# untitled.net
KiCad netlist of a schematic drawn in EAGLE
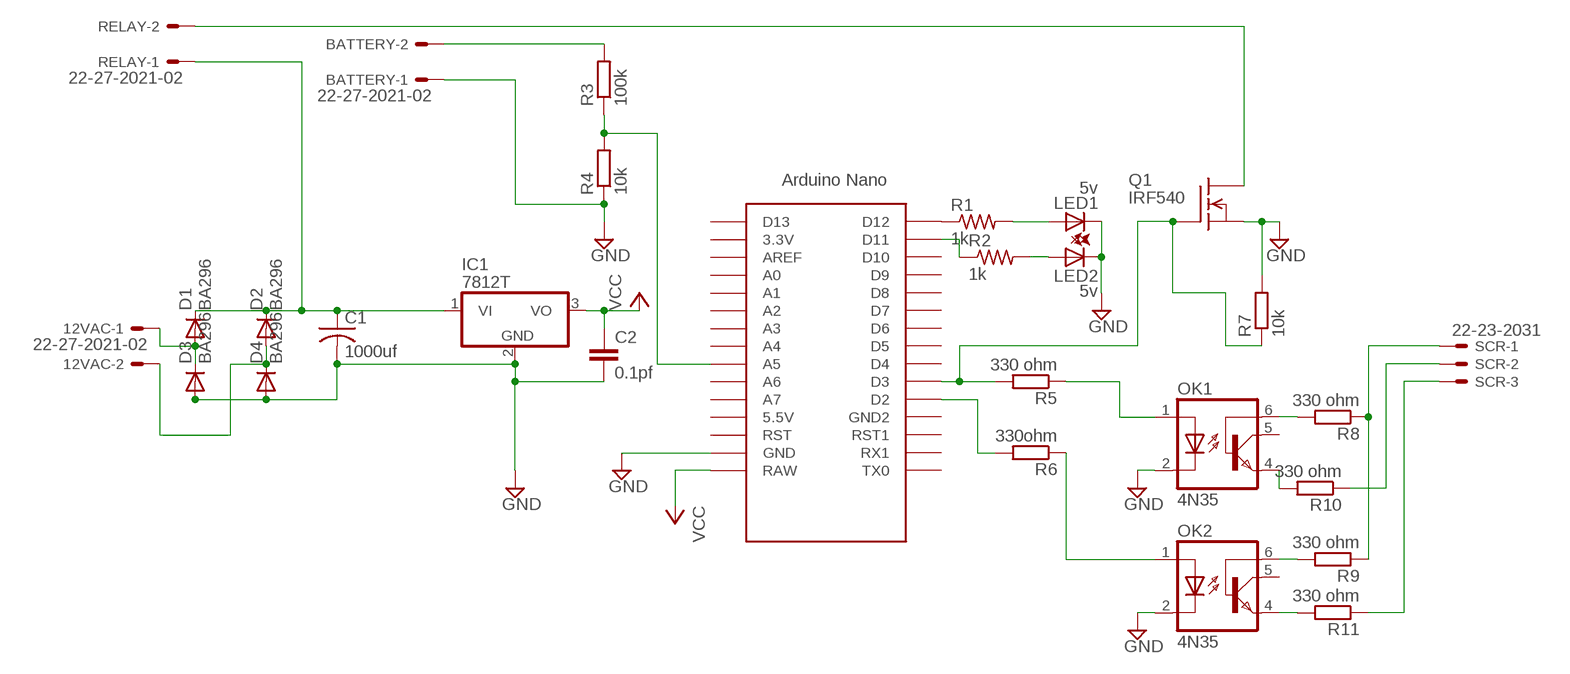
[diagram p0: schematic, sheet 1]

(export (version "E")
  (design (tool "Eeschema 10.0.6"))
  (components
    (comp (ref "12VAC")
      (value "22-27-2021-02")
      (footprint "eagle-import:6410-02")
      (libsource (lib "eagle-import") (part "22-?-0227-2021"))
    )
    (comp (ref "BATTERY")
      (value "22-27-2021-02")
      (footprint "eagle-import:6410-02")
      (libsource (lib "eagle-import") (part "22-?-0227-2021"))
    )
    (comp (ref "C1")
      (value "1000uf")
      (footprint "eagle-import:C050-025X075")
      (libsource (lib "eagle-import") (part "C-US050-025X075"))
    )
    (comp (ref "C2")
      (value "0.1pf")
      (footprint "eagle-import:C7.5B4")
      (libsource (lib "eagle-import") (part "C7.5/4"))
    )
    (comp (ref "D1")
      (value "BA296")
      (footprint "eagle-import:P2-15")
      (libsource (lib "eagle-import") (part "BA296"))
    )
    (comp (ref "D2")
      (value "BA296")
      (footprint "eagle-import:P2-15")
      (libsource (lib "eagle-import") (part "BA296"))
    )
    (comp (ref "D3")
      (value "BA296")
      (footprint "eagle-import:P2-15")
      (libsource (lib "eagle-import") (part "BA296"))
    )
    (comp (ref "D4")
      (value "BA296")
      (footprint "eagle-import:P2-15")
      (libsource (lib "eagle-import") (part "BA296"))
    )
    (comp (ref "IC1")
      (value "7812T")
      (footprint "eagle-import:TO220H")
      (libsource (lib "eagle-import") (part "78T12"))
    )
    (comp (ref "LED1")
      (value "5v")
      (footprint "eagle-import:LED_1206")
      (libsource (lib "eagle-import") (part "LED_E"))
    )
    (comp (ref "LED2")
      (value "5v")
      (footprint "eagle-import:LED_1206")
      (libsource (lib "eagle-import") (part "LED_E"))
    )
    (comp (ref "OK1")
      (value "4N35")
      (footprint "eagle-import:DIL06")
      (fields (field (name "MF") "FAIRCHILD SEMICONDUCTOR"))
      (libsource (lib "eagle-import") (part "4N35"))
    )
    (comp (ref "OK2")
      (value "4N35")
      (footprint "eagle-import:DIL06")
      (fields (field (name "MF") "FAIRCHILD SEMICONDUCTOR"))
      (libsource (lib "eagle-import") (part "4N35"))
    )
    (comp (ref "Q1")
      (value "IRF540")
      (footprint "eagle-import:TO220")
      (libsource (lib "eagle-import") (part "IRF540"))
    )
    (comp (ref "R1")
      (value "1k")
      (footprint "eagle-import:0207_2V")
      (libsource (lib "eagle-import") (part "R-US_0207/2V"))
    )
    (comp (ref "R2")
      (value "1k")
      (footprint "eagle-import:0207_2V")
      (libsource (lib "eagle-import") (part "R-US_0207/2V"))
    )
    (comp (ref "R3")
      (value "100k")
      (footprint "eagle-import:0207_10")
      (libsource (lib "eagle-import") (part "R0207/10"))
    )
    (comp (ref "R4")
      (value "10k")
      (footprint "eagle-import:0207_10")
      (libsource (lib "eagle-import") (part "R0207/10"))
    )
    (comp (ref "R5")
      (value "330 ohm")
      (footprint "eagle-import:0207_10")
      (libsource (lib "eagle-import") (part "R0207/10"))
    )
    (comp (ref "R6")
      (value "330ohm")
      (footprint "eagle-import:0207_10")
      (libsource (lib "eagle-import") (part "R0207/10"))
    )
    (comp (ref "R7")
      (value "10k")
      (footprint "eagle-import:0207_10")
      (libsource (lib "eagle-import") (part "R0207/10"))
    )
    (comp (ref "R8")
      (value "330 ohm")
      (footprint "eagle-import:0207_10")
      (libsource (lib "eagle-import") (part "R0207/10"))
    )
    (comp (ref "R9")
      (value "330 ohm")
      (footprint "eagle-import:0207_10")
      (libsource (lib "eagle-import") (part "R0207/10"))
    )
    (comp (ref "R10")
      (value "330 ohm")
      (footprint "eagle-import:0207_10")
      (libsource (lib "eagle-import") (part "R0207/10"))
    )
    (comp (ref "R11")
      (value "330 ohm")
      (footprint "eagle-import:0207_10")
      (libsource (lib "eagle-import") (part "R0207/10"))
    )
    (comp (ref "RELAY")
      (value "22-27-2021-02")
      (footprint "eagle-import:6410-02")
      (libsource (lib "eagle-import") (part "22-?-0227-2021"))
    )
    (comp (ref "SCR")
      (value "22-23-2031")
      (footprint "eagle-import:22-23-2031")
      (fields (field (name "MF") "MOLEX"))
      (libsource (lib "eagle-import") (part "22-23-2031"))
    )
    (comp (ref "U$1")
      (value "NANO")
      (footprint "eagle-import:NANO")
      (libsource (lib "eagle-import") (part "NANO"))
    )
  )
  (nets
    (net (code "1") (name "GND") (class "Default")
      (node (ref "BATTERY") (pin "1") (pinfunction "S_1") (pintype "passive"))
      (node (ref "C1") (pin "2") (pinfunction "2_2") (pintype "passive"))
      (node (ref "C2") (pin "2") (pinfunction "2_2") (pintype "passive"))
      (node (ref "D3") (pin "A") (pinfunction "A_A") (pintype "passive"))
      (node (ref "D4") (pin "A") (pinfunction "A_A") (pintype "passive"))
      (node (ref "IC1") (pin "2") (pinfunction "GND_2") (pintype "passive"))
      (node (ref "LED1") (pin "C") (pinfunction "C_C") (pintype "passive"))
      (node (ref "LED2") (pin "C") (pinfunction "C_C") (pintype "passive"))
      (node (ref "OK1") (pin "2") (pinfunction "C_2") (pintype "passive"))
      (node (ref "OK2") (pin "2") (pinfunction "C_2") (pintype "passive"))
      (node (ref "Q1") (pin "3") (pinfunction "S_3") (pintype "passive"))
      (node (ref "R4") (pin "1") (pinfunction "1_1") (pintype "passive"))
      (node (ref "R7") (pin "2") (pinfunction "2_2") (pintype "passive"))
      (node (ref "U$1") (pin "GND") (pinfunction "GND_GND") (pintype "bidirectional"))
    )
    (net (code "2") (name "Net-(12VACA-S)") (class "Default")
      (node (ref "12VAC") (pin "1") (pinfunction "S_1") (pintype "passive"))
      (node (ref "D1") (pin "A") (pinfunction "A_A") (pintype "passive"))
      (node (ref "D3") (pin "C") (pinfunction "C_C") (pintype "passive"))
    )
    (net (code "3") (name "Net-(12VACB-S)") (class "Default")
      (node (ref "12VAC") (pin "2") (pinfunction "S_2") (pintype "passive"))
      (node (ref "D2") (pin "A") (pinfunction "A_A") (pintype "passive"))
      (node (ref "D4") (pin "C") (pinfunction "C_C") (pintype "passive"))
    )
    (net (code "4") (name "Net-(BATTERYB-S)") (class "Default")
      (node (ref "BATTERY") (pin "2") (pinfunction "S_2") (pintype "passive"))
      (node (ref "R3") (pin "2") (pinfunction "2_2") (pintype "passive"))
    )
    (net (code "5") (name "Net-(IC1-VI)") (class "Default")
      (node (ref "C1") (pin "1") (pinfunction "1_1") (pintype "passive"))
      (node (ref "D1") (pin "C") (pinfunction "C_C") (pintype "passive"))
      (node (ref "D2") (pin "C") (pinfunction "C_C") (pintype "passive"))
      (node (ref "IC1") (pin "1") (pinfunction "VI_1") (pintype "input"))
      (node (ref "RELAY") (pin "1") (pinfunction "S_1") (pintype "passive"))
    )
    (net (code "6") (name "Net-(LED1-PadA)") (class "Default")
      (node (ref "LED1") (pin "A") (pinfunction "A_A") (pintype "passive"))
      (node (ref "R1") (pin "2") (pinfunction "2_2") (pintype "passive"))
    )
    (net (code "7") (name "Net-(LED2-PadA)") (class "Default")
      (node (ref "LED2") (pin "A") (pinfunction "A_A") (pintype "passive"))
      (node (ref "R2") (pin "2") (pinfunction "2_2") (pintype "passive"))
    )
    (net (code "8") (name "Net-(OK1-A)") (class "Default")
      (node (ref "OK1") (pin "1") (pinfunction "A_1") (pintype "passive"))
      (node (ref "R5") (pin "1") (pinfunction "1_1") (pintype "passive"))
    )
    (net (code "9") (name "Net-(OK1-BAS)") (class "Default")
      (node (ref "OK1") (pin "6") (pinfunction "BAS_6") (pintype "passive"))
      (node (ref "R8") (pin "2") (pinfunction "2_2") (pintype "passive"))
    )
    (net (code "10") (name "Net-(OK1-EMI)") (class "Default")
      (node (ref "OK1") (pin "4") (pinfunction "EMI_4") (pintype "passive"))
      (node (ref "R10") (pin "2") (pinfunction "2_2") (pintype "passive"))
    )
    (net (code "11") (name "Net-(OK2-A)") (class "Default")
      (node (ref "OK2") (pin "1") (pinfunction "A_1") (pintype "passive"))
      (node (ref "R6") (pin "1") (pinfunction "1_1") (pintype "passive"))
    )
    (net (code "12") (name "Net-(OK2-BAS)") (class "Default")
      (node (ref "OK2") (pin "6") (pinfunction "BAS_6") (pintype "passive"))
      (node (ref "R9") (pin "2") (pinfunction "2_2") (pintype "passive"))
    )
    (net (code "13") (name "Net-(OK2-EMI)") (class "Default")
      (node (ref "OK2") (pin "4") (pinfunction "EMI_4") (pintype "passive"))
      (node (ref "R11") (pin "2") (pinfunction "2_2") (pintype "passive"))
    )
    (net (code "14") (name "Net-(Q1-D)") (class "Default")
      (node (ref "Q1") (pin "2") (pinfunction "D_2") (pintype "passive"))
      (node (ref "RELAY") (pin "2") (pinfunction "S_2") (pintype "passive"))
    )
    (net (code "15") (name "Net-(Q1-G)") (class "Default")
      (node (ref "Q1") (pin "1") (pinfunction "G_1") (pintype "passive"))
      (node (ref "R5") (pin "2") (pinfunction "2_2") (pintype "passive"))
      (node (ref "R7") (pin "1") (pinfunction "1_1") (pintype "passive"))
      (node (ref "U$1") (pin "D3") (pinfunction "D3_D3") (pintype "bidirectional"))
    )
    (net (code "16") (name "Net-(R1-Pad1)") (class "Default")
      (node (ref "R1") (pin "1") (pinfunction "1_1") (pintype "passive"))
      (node (ref "U$1") (pin "D12") (pinfunction "D12_D12") (pintype "bidirectional"))
    )
    (net (code "17") (name "Net-(R2-Pad1)") (class "Default")
      (node (ref "R2") (pin "1") (pinfunction "1_1") (pintype "passive"))
      (node (ref "U$1") (pin "D11") (pinfunction "D11_D11") (pintype "bidirectional"))
    )
    (net (code "18") (name "Net-(R3-Pad1)") (class "Default")
      (node (ref "R3") (pin "1") (pinfunction "1_1") (pintype "passive"))
      (node (ref "R4") (pin "2") (pinfunction "2_2") (pintype "passive"))
      (node (ref "U$1") (pin "A5") (pinfunction "A5_A5") (pintype "bidirectional"))
    )
    (net (code "19") (name "Net-(R6-Pad2)") (class "Default")
      (node (ref "R6") (pin "2") (pinfunction "2_2") (pintype "passive"))
      (node (ref "U$1") (pin "D2") (pinfunction "D2_D2") (pintype "bidirectional"))
    )
    (net (code "20") (name "Net-(SCRA-S)") (class "Default")
      (node (ref "R8") (pin "1") (pinfunction "1_1") (pintype "passive"))
      (node (ref "R9") (pin "1") (pinfunction "1_1") (pintype "passive"))
      (node (ref "SCR") (pin "1") (pinfunction "S_1") (pintype "passive"))
    )
    (net (code "21") (name "Net-(SCRB-S)") (class "Default")
      (node (ref "R10") (pin "1") (pinfunction "1_1") (pintype "passive"))
      (node (ref "SCR") (pin "2") (pinfunction "S_2") (pintype "passive"))
    )
    (net (code "22") (name "Net-(SCRC-S)") (class "Default")
      (node (ref "R11") (pin "1") (pinfunction "1_1") (pintype "passive"))
      (node (ref "SCR") (pin "3") (pinfunction "S_3") (pintype "passive"))
    )
    (net (code "23") (name "VCC") (class "Default")
      (node (ref "C2") (pin "1") (pinfunction "1_1") (pintype "passive"))
      (node (ref "IC1") (pin "3") (pinfunction "VO_3") (pintype "passive"))
      (node (ref "U$1") (pin "RAW") (pinfunction "RAW_RAW") (pintype "bidirectional"))
    )
    (net (code "24") (name "unconnected-(OK1-COL-Pad5)") (class "Default")
      (node (ref "OK1") (pin "5") (pinfunction "COL_5") (pintype "passive"))
    )
    (net (code "25") (name "unconnected-(OK2-COL-Pad5)") (class "Default")
      (node (ref "OK2") (pin "5") (pinfunction "COL_5") (pintype "passive"))
    )
    (net (code "26") (name "unconnected-(U$1-5.5V-Pad5V)") (class "Default")
      (node (ref "U$1") (pin "5V") (pinfunction "5.5V_5V") (pintype "bidirectional"))
    )
    (net (code "27") (name "unconnected-(U$1-GND2-PadGND1)") (class "Default")
      (node (ref "U$1") (pin "GND1") (pinfunction "GND2_GND1") (pintype "bidirectional"))
    )
    (net (code "28") (name "unconnected-(U$1-Pad3.3V)") (class "Default")
      (node (ref "U$1") (pin "3.3V") (pinfunction "3.3V_3.3V") (pintype "bidirectional"))
    )
    (net (code "29") (name "unconnected-(U$1-PadA0)") (class "Default")
      (node (ref "U$1") (pin "A0") (pinfunction "A0_A0") (pintype "bidirectional"))
    )
    (net (code "30") (name "unconnected-(U$1-PadA1)") (class "Default")
      (node (ref "U$1") (pin "A1") (pinfunction "A1_A1") (pintype "bidirectional"))
    )
    (net (code "31") (name "unconnected-(U$1-PadA2)") (class "Default")
      (node (ref "U$1") (pin "A2") (pinfunction "A2_A2") (pintype "bidirectional"))
    )
    (net (code "32") (name "unconnected-(U$1-PadA3)") (class "Default")
      (node (ref "U$1") (pin "A3") (pinfunction "A3_A3") (pintype "bidirectional"))
    )
    (net (code "33") (name "unconnected-(U$1-PadA4)") (class "Default")
      (node (ref "U$1") (pin "A4") (pinfunction "A4_A4") (pintype "bidirectional"))
    )
    (net (code "34") (name "unconnected-(U$1-PadA6)") (class "Default")
      (node (ref "U$1") (pin "A6") (pinfunction "A6_A6") (pintype "bidirectional"))
    )
    (net (code "35") (name "unconnected-(U$1-PadA7)") (class "Default")
      (node (ref "U$1") (pin "A7") (pinfunction "A7_A7") (pintype "bidirectional"))
    )
    (net (code "36") (name "unconnected-(U$1-PadAREF)") (class "Default")
      (node (ref "U$1") (pin "AREF") (pinfunction "AREF_AREF") (pintype "bidirectional"))
    )
    (net (code "37") (name "unconnected-(U$1-PadD4)") (class "Default")
      (node (ref "U$1") (pin "D4") (pinfunction "D4_D4") (pintype "bidirectional"))
    )
    (net (code "38") (name "unconnected-(U$1-PadD5)") (class "Default")
      (node (ref "U$1") (pin "D5") (pinfunction "D5_D5") (pintype "bidirectional"))
    )
    (net (code "39") (name "unconnected-(U$1-PadD6)") (class "Default")
      (node (ref "U$1") (pin "D6") (pinfunction "D6_D6") (pintype "bidirectional"))
    )
    (net (code "40") (name "unconnected-(U$1-PadD7)") (class "Default")
      (node (ref "U$1") (pin "D7") (pinfunction "D7_D7") (pintype "bidirectional"))
    )
    (net (code "41") (name "unconnected-(U$1-PadD8)") (class "Default")
      (node (ref "U$1") (pin "D8") (pinfunction "D8_D8") (pintype "bidirectional"))
    )
    (net (code "42") (name "unconnected-(U$1-PadD9)") (class "Default")
      (node (ref "U$1") (pin "D9") (pinfunction "D9_D9") (pintype "bidirectional"))
    )
    (net (code "43") (name "unconnected-(U$1-PadD10)") (class "Default")
      (node (ref "U$1") (pin "D10") (pinfunction "D10_D10") (pintype "bidirectional"))
    )
    (net (code "44") (name "unconnected-(U$1-PadD13)") (class "Default")
      (node (ref "U$1") (pin "D13") (pinfunction "D13_D13") (pintype "bidirectional"))
    )
    (net (code "45") (name "unconnected-(U$1-PadICSP1)") (class "Default")
      (node (ref "U$1") (pin "ICSP1") (pinfunction "ICSP1_ICSP1") (pintype "bidirectional"))
    )
    (net (code "46") (name "unconnected-(U$1-PadICSP2)") (class "Default")
      (node (ref "U$1") (pin "ICSP2") (pinfunction "ICSP2_ICSP2") (pintype "bidirectional"))
    )
    (net (code "47") (name "unconnected-(U$1-PadICSP3)") (class "Default")
      (node (ref "U$1") (pin "ICSP3") (pinfunction "ICSP3_ICSP3") (pintype "bidirectional"))
    )
    (net (code "48") (name "unconnected-(U$1-PadICSP4)") (class "Default")
      (node (ref "U$1") (pin "ICSP4") (pinfunction "ICSP4_ICSP4") (pintype "bidirectional"))
    )
    (net (code "49") (name "unconnected-(U$1-PadICSP5)") (class "Default")
      (node (ref "U$1") (pin "ICSP5") (pinfunction "ICSP5_ICSP5") (pintype "bidirectional"))
    )
    (net (code "50") (name "unconnected-(U$1-PadICSP6)") (class "Default")
      (node (ref "U$1") (pin "ICSP6") (pinfunction "ICSP6_ICSP6") (pintype "bidirectional"))
    )
    (net (code "51") (name "unconnected-(U$1-PadRST)") (class "Default")
      (node (ref "U$1") (pin "RST") (pinfunction "RST_RST") (pintype "bidirectional"))
    )
    (net (code "52") (name "unconnected-(U$1-PadRST1)") (class "Default")
      (node (ref "U$1") (pin "RST1") (pinfunction "RST1_RST1") (pintype "bidirectional"))
    )
    (net (code "53") (name "unconnected-(U$1-PadRX1)") (class "Default")
      (node (ref "U$1") (pin "RX1") (pinfunction "RX1_RX1") (pintype "bidirectional"))
    )
    (net (code "54") (name "unconnected-(U$1-PadTX0)") (class "Default")
      (node (ref "U$1") (pin "TX0") (pinfunction "TX0_TX0") (pintype "bidirectional"))
    )
  )
)
